# module.net
KiCad netlist of a schematic drawn in EAGLE
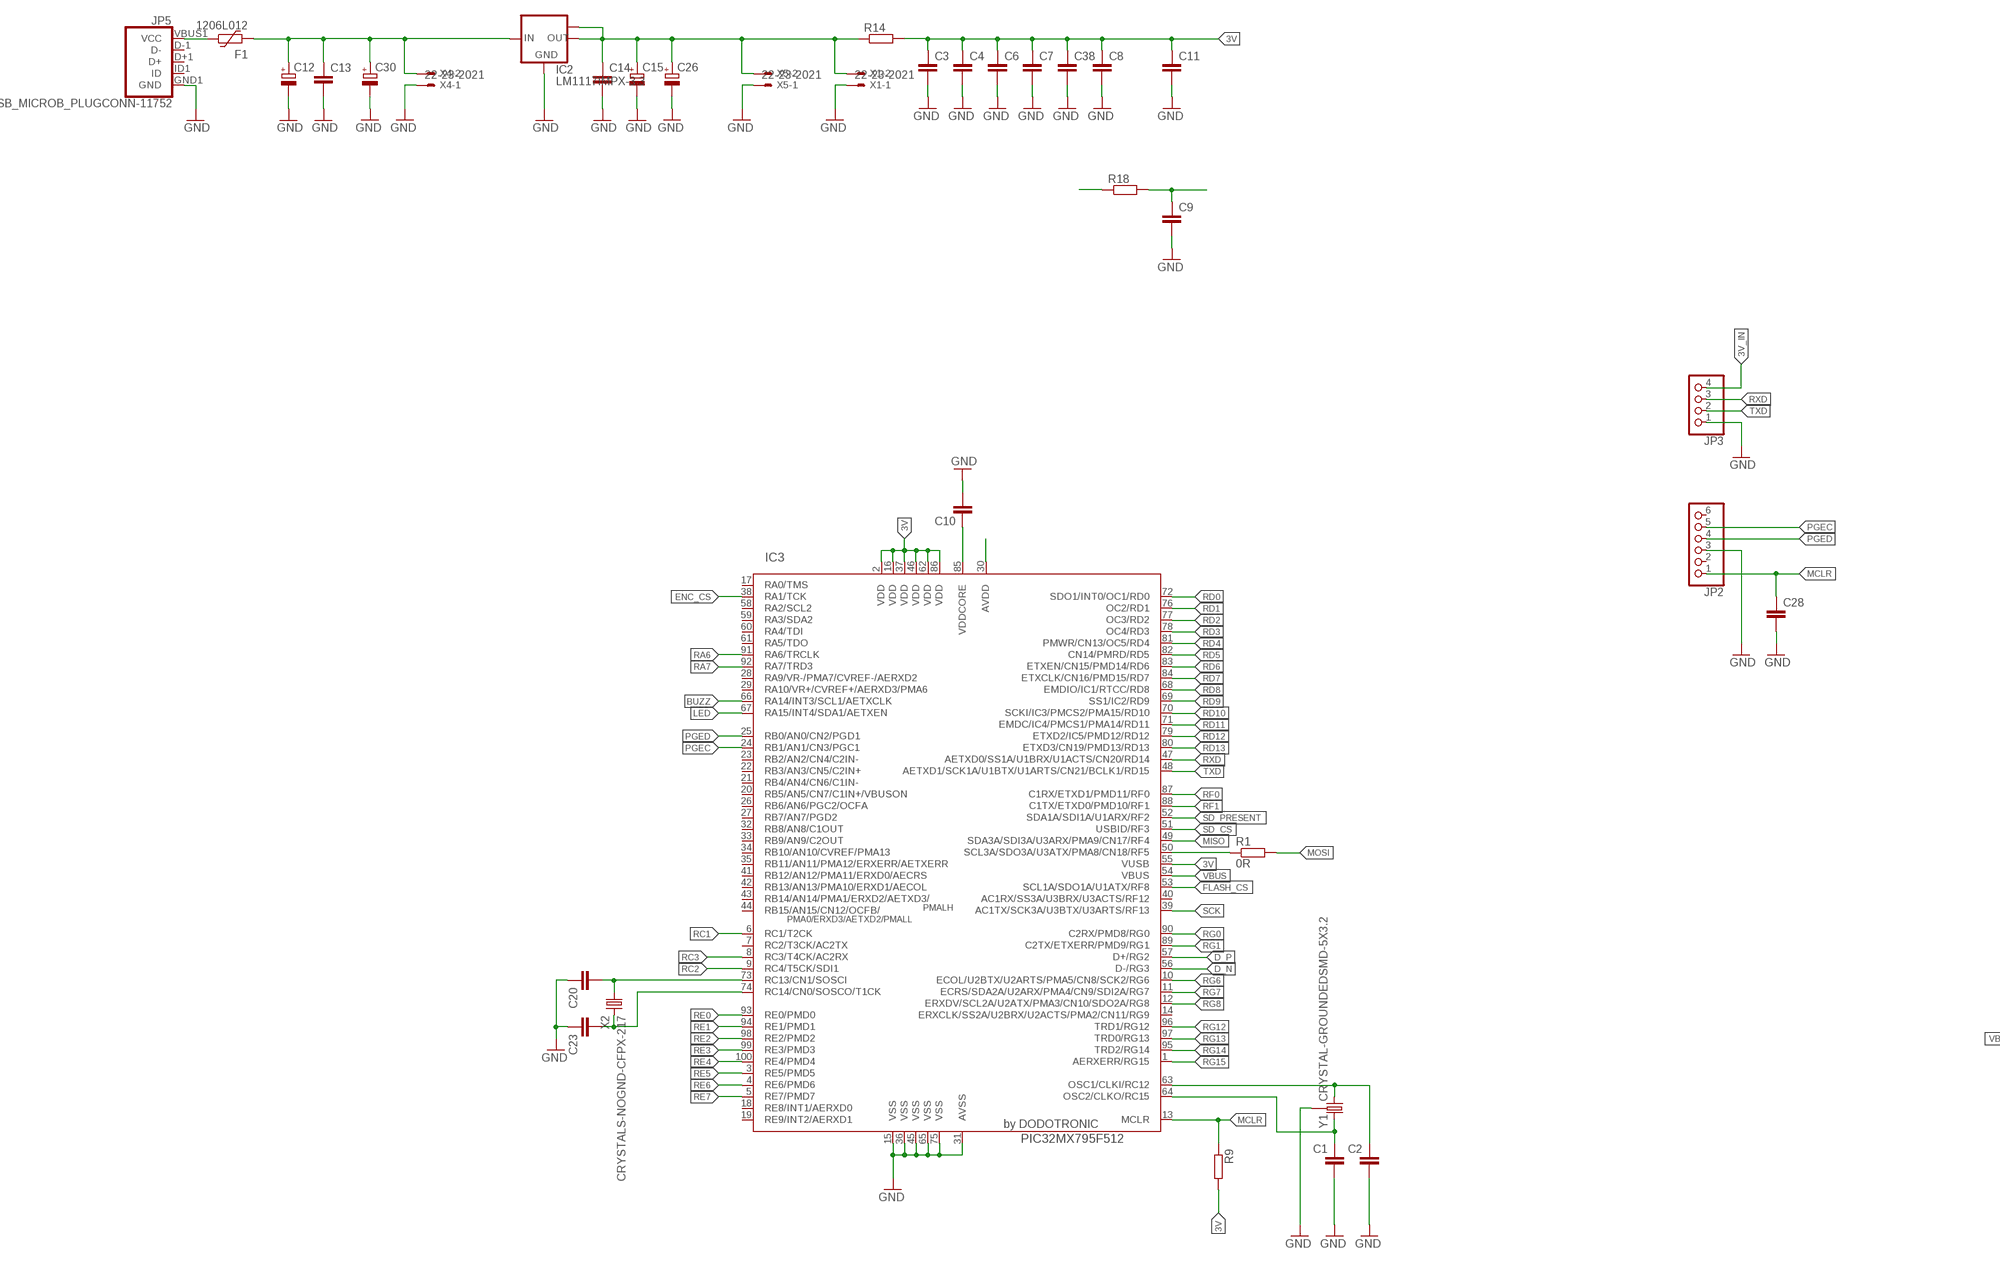
[diagram p0: schematic, sheet 1, part 1 of 3]
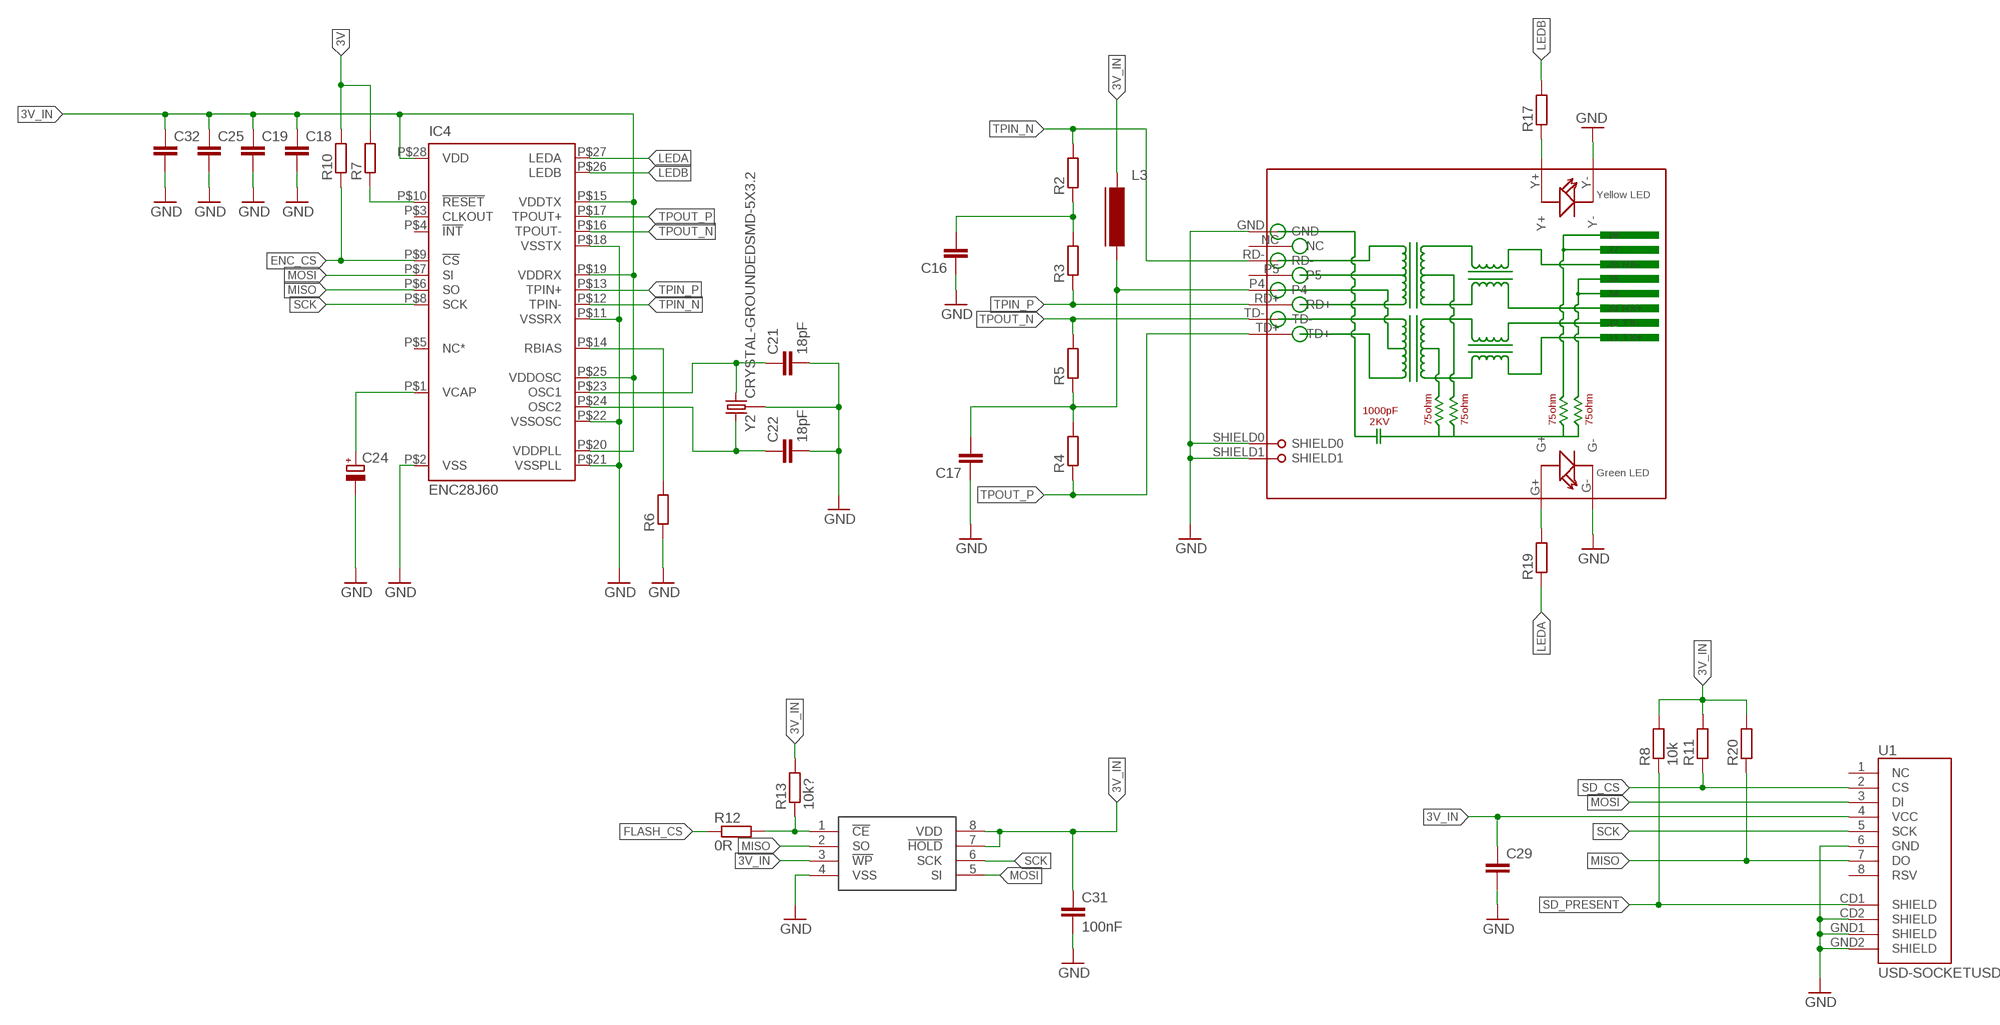
[diagram p1: schematic, sheet 1, part 2 of 3]
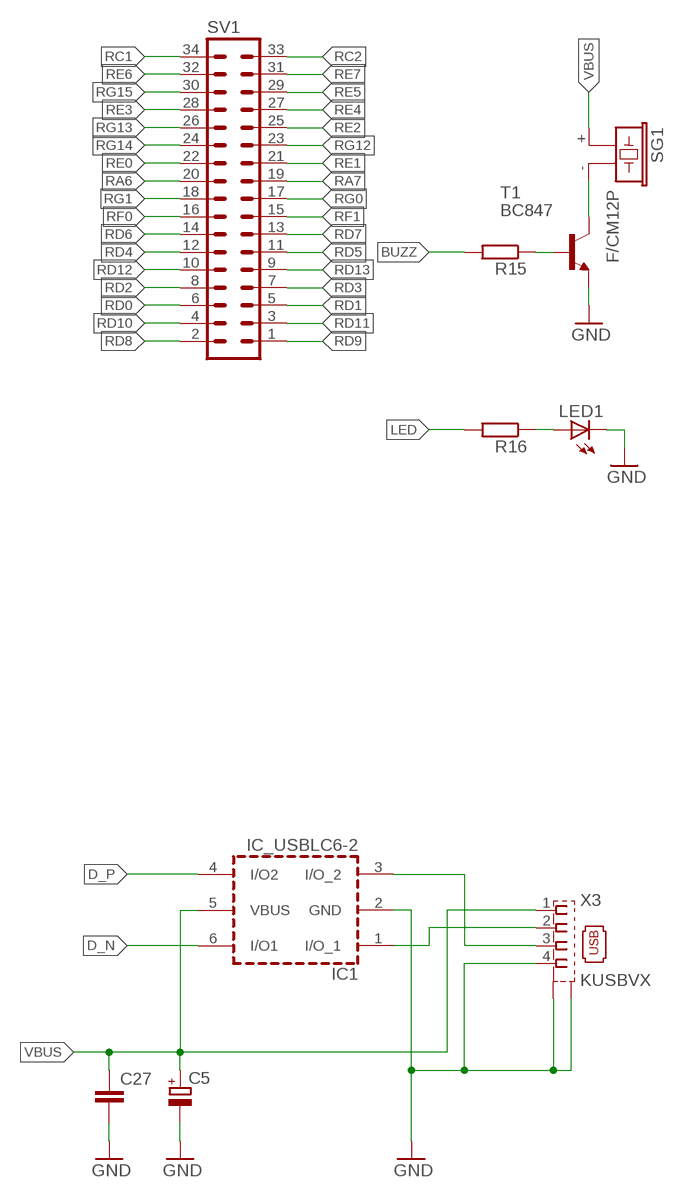
[diagram p2: schematic, sheet 1, part 3 of 3]

(export (version "E")
  (design (tool "Eeschema 10.0.6"))
  (components
    (comp (ref "C1")
      (value "C-EUC0603")
      (footprint "eagle-import:C0603")
      (libsource (lib "eagle-import") (part "C-EUC0603"))
    )
    (comp (ref "C2")
      (value "C-EUC0603")
      (footprint "eagle-import:C0603")
      (libsource (lib "eagle-import") (part "C-EUC0603"))
    )
    (comp (ref "C3")
      (value "C-EUC0402")
      (footprint "eagle-import:C0402")
      (libsource (lib "eagle-import") (part "C-EUC0402"))
    )
    (comp (ref "C4")
      (value "C-EUC0402")
      (footprint "eagle-import:C0402")
      (libsource (lib "eagle-import") (part "C-EUC0402"))
    )
    (comp (ref "C5")
      (value "CPOL-EUSMCA")
      (footprint "eagle-import:SMC_A")
      (libsource (lib "eagle-import") (part "CPOL-EUSMCA"))
    )
    (comp (ref "C6")
      (value "C-EUC0402")
      (footprint "eagle-import:C0402")
      (libsource (lib "eagle-import") (part "C-EUC0402"))
    )
    (comp (ref "C7")
      (value "C-EUC0402")
      (footprint "eagle-import:C0402")
      (libsource (lib "eagle-import") (part "C-EUC0402"))
    )
    (comp (ref "C8")
      (value "C-EUC0402")
      (footprint "eagle-import:C0402")
      (libsource (lib "eagle-import") (part "C-EUC0402"))
    )
    (comp (ref "C9")
      (value "C-EUC0402")
      (footprint "eagle-import:C0402")
      (libsource (lib "eagle-import") (part "C-EUC0402"))
    )
    (comp (ref "C10")
      (value "C-EUC0603")
      (footprint "eagle-import:C0603")
      (libsource (lib "eagle-import") (part "C-EUC0603"))
    )
    (comp (ref "C11")
      (value "C-EUC0402")
      (footprint "eagle-import:C0402")
      (libsource (lib "eagle-import") (part "C-EUC0402"))
    )
    (comp (ref "C12")
      (value "CPOL-EUSMCB")
      (footprint "eagle-import:SMC_B")
      (libsource (lib "eagle-import") (part "CPOL-EUSMCB"))
    )
    (comp (ref "C13")
      (value "C-EUC0603")
      (footprint "eagle-import:C0603")
      (libsource (lib "eagle-import") (part "C-EUC0603"))
    )
    (comp (ref "C14")
      (value "C-EUC0603")
      (footprint "eagle-import:C0603")
      (libsource (lib "eagle-import") (part "C-EUC0603"))
    )
    (comp (ref "C15")
      (value "CPOL-EUSMCB")
      (footprint "eagle-import:SMC_B")
      (libsource (lib "eagle-import") (part "CPOL-EUSMCB"))
    )
    (comp (ref "C16")
      (value "C-EUC0603")
      (footprint "eagle-import:C0603")
      (libsource (lib "eagle-import") (part "C-EUC0603"))
    )
    (comp (ref "C17")
      (value "C-EUC0603")
      (footprint "eagle-import:C0603")
      (libsource (lib "eagle-import") (part "C-EUC0603"))
    )
    (comp (ref "C18")
      (value "C-EUC0402")
      (footprint "eagle-import:C0402")
      (libsource (lib "eagle-import") (part "C-EUC0402"))
    )
    (comp (ref "C19")
      (value "C-EUC0603")
      (footprint "eagle-import:C0603")
      (libsource (lib "eagle-import") (part "C-EUC0603"))
    )
    (comp (ref "C20")
      (value "C-EUC0603")
      (footprint "eagle-import:C0603")
      (libsource (lib "eagle-import") (part "C-EUC0603"))
    )
    (comp (ref "C21")
      (value "18pF")
      (footprint "eagle-import:C0603")
      (libsource (lib "eagle-import") (part "C-EUC0603"))
    )
    (comp (ref "C22")
      (value "18pF")
      (footprint "eagle-import:C0603")
      (libsource (lib "eagle-import") (part "C-EUC0603"))
    )
    (comp (ref "C23")
      (value "C-EUC0603")
      (footprint "eagle-import:C0603")
      (libsource (lib "eagle-import") (part "C-EUC0603"))
    )
    (comp (ref "C24")
      (value "CPOL-EUSMCA")
      (footprint "eagle-import:SMC_A")
      (libsource (lib "eagle-import") (part "CPOL-EUSMCA"))
    )
    (comp (ref "C25")
      (value "C-EUC0603")
      (footprint "eagle-import:C0603")
      (libsource (lib "eagle-import") (part "C-EUC0603"))
    )
    (comp (ref "C26")
      (value "CPOL-EUSMCA")
      (footprint "eagle-import:SMC_A")
      (libsource (lib "eagle-import") (part "CPOL-EUSMCA"))
    )
    (comp (ref "C27")
      (value "C-EUC0603")
      (footprint "eagle-import:C0603")
      (libsource (lib "eagle-import") (part "C-EUC0603"))
    )
    (comp (ref "C28")
      (value "C-EUC0603")
      (footprint "eagle-import:C0603")
      (libsource (lib "eagle-import") (part "C-EUC0603"))
    )
    (comp (ref "C29")
      (value "C-EUC0603")
      (footprint "eagle-import:C0603")
      (libsource (lib "eagle-import") (part "C-EUC0603"))
    )
    (comp (ref "C30")
      (value "CPOL-EUSMCA")
      (footprint "eagle-import:SMC_A")
      (libsource (lib "eagle-import") (part "CPOL-EUSMCA"))
    )
    (comp (ref "C31")
      (value "100nF")
      (footprint "eagle-import:C0603")
      (libsource (lib "eagle-import") (part "C-EUC0603"))
    )
    (comp (ref "C32")
      (value "C-EUC0402")
      (footprint "eagle-import:C0402")
      (libsource (lib "eagle-import") (part "C-EUC0402"))
    )
    (comp (ref "C38")
      (value "C-EUC0603")
      (footprint "eagle-import:C0603")
      (libsource (lib "eagle-import") (part "C-EUC0603"))
    )
    (comp (ref "F1")
      (value "1206L012")
      (footprint "eagle-import:1206L")
      (fields (field (name "MF") "Littelfuse"))
      (libsource (lib "eagle-import") (part "?1206L012"))
    )
    (comp (ref "IC1")
      (value "IC_USBLC6-2")
      (footprint "eagle-import:SOT-23-6L")
      (libsource (lib "eagle-import") (part "IC_USBLC6-2"))
    )
    (comp (ref "IC2")
      (value "LM1117IMPX-3.3")
      (footprint "eagle-import:SOT223")
      (libsource (lib "eagle-import") (part "LM1117IMPX-3.3"))
    )
    (comp (ref "IC3")
      (value "PIC32MX795F512")
      (footprint "eagle-import:TQFP100_12X12")
      (libsource (lib "eagle-import") (part "PIC32MX795F512"))
    )
    (comp (ref "IC4")
      (value "ENC28J60")
      (footprint "eagle-import:TSSOP28W")
      (libsource (lib "eagle-import") (part "ENC28J60"))
    )
    (comp (ref "JP2")
      (value "PINHD-1X6")
      (footprint "eagle-import:1X06")
      (libsource (lib "eagle-import") (part "PINHD-1X6"))
    )
    (comp (ref "JP3")
      (value "PINHD-1X4")
      (footprint "eagle-import:1X04")
      (libsource (lib "eagle-import") (part "PINHD-1X4"))
    )
    (comp (ref "JP5")
      (value "USB_MICROB_PLUGCONN-11752")
      (footprint "eagle-import:USB-B-MICRO-SMD_V03")
      (libsource (lib "eagle-import") (part "USB_MICROB_PLUGCONN-11752"))
    )
    (comp (ref "L3")
      (value "FERRITE-0805")
      (footprint "eagle-import:FB805")
      (libsource (lib "eagle-import") (part "FERRITE-0805"))
    )
    (comp (ref "LED1")
      (value "LED3MM")
      (footprint "eagle-import:LED3MM")
      (libsource (lib "eagle-import") (part "LED3MM"))
    )
    (comp (ref "R1")
      (value "0R")
      (footprint "eagle-import:R0603")
      (libsource (lib "eagle-import") (part "R-EU_R0603"))
    )
    (comp (ref "R2")
      (value "R-EU_R0603")
      (footprint "eagle-import:R0603")
      (libsource (lib "eagle-import") (part "R-EU_R0603"))
    )
    (comp (ref "R3")
      (value "R-EU_R0603")
      (footprint "eagle-import:R0603")
      (libsource (lib "eagle-import") (part "R-EU_R0603"))
    )
    (comp (ref "R4")
      (value "R-EU_R0603")
      (footprint "eagle-import:R0603")
      (libsource (lib "eagle-import") (part "R-EU_R0603"))
    )
    (comp (ref "R5")
      (value "R-EU_R0603")
      (footprint "eagle-import:R0603")
      (libsource (lib "eagle-import") (part "R-EU_R0603"))
    )
    (comp (ref "R6")
      (value "R-EU_R0805")
      (footprint "eagle-import:R0805")
      (libsource (lib "eagle-import") (part "R-EU_R0805"))
    )
    (comp (ref "R7")
      (value "R-EU_R0402")
      (footprint "eagle-import:R0402")
      (libsource (lib "eagle-import") (part "R-EU_R0402"))
    )
    (comp (ref "R8")
      (value "10k")
      (footprint "eagle-import:R0603")
      (libsource (lib "eagle-import") (part "R-EU_R0603"))
    )
    (comp (ref "R9")
      (value "R-EU_R0603")
      (footprint "eagle-import:R0603")
      (libsource (lib "eagle-import") (part "R-EU_R0603"))
    )
    (comp (ref "R10")
      (value "R-EU_R0603")
      (footprint "eagle-import:R0603")
      (libsource (lib "eagle-import") (part "R-EU_R0603"))
    )
    (comp (ref "R11")
      (value "R-EU_R0603")
      (footprint "eagle-import:R0603")
      (libsource (lib "eagle-import") (part "R-EU_R0603"))
    )
    (comp (ref "R12")
      (value "0R")
      (footprint "eagle-import:R0603")
      (libsource (lib "eagle-import") (part "R-EU_R0603"))
    )
    (comp (ref "R13")
      (value "10k?")
      (footprint "eagle-import:R0603")
      (libsource (lib "eagle-import") (part "R-EU_R0603"))
    )
    (comp (ref "R14")
      (value "R-EU_R1206")
      (footprint "eagle-import:R1206")
      (libsource (lib "eagle-import") (part "R-EU_R1206"))
    )
    (comp (ref "R15")
      (value "R-EU_R0603")
      (footprint "eagle-import:R0603")
      (libsource (lib "eagle-import") (part "R-EU_R0603"))
    )
    (comp (ref "R16")
      (value "R-EU_R0603")
      (footprint "eagle-import:R0603")
      (libsource (lib "eagle-import") (part "R-EU_R0603"))
    )
    (comp (ref "R17")
      (value "R-EU_R1206")
      (footprint "eagle-import:R1206")
      (libsource (lib "eagle-import") (part "R-EU_R1206"))
    )
    (comp (ref "R18")
      (value "R-EU_R0805")
      (footprint "eagle-import:R0805")
      (libsource (lib "eagle-import") (part "R-EU_R0805"))
    )
    (comp (ref "R19")
      (value "R-EU_R1206")
      (footprint "eagle-import:R1206")
      (libsource (lib "eagle-import") (part "R-EU_R1206"))
    )
    (comp (ref "R20")
      (value "R-EU_R0603")
      (footprint "eagle-import:R0603")
      (libsource (lib "eagle-import") (part "R-EU_R0603"))
    )
    (comp (ref "RJ1")
      (value "HR911105A")
      (footprint "eagle-import:HR911105A")
      (libsource (lib "eagle-import") (part "HR911105A"))
    )
    (comp (ref "SG1")
      (value "F/CM12P")
      (footprint "eagle-import:F_CM12P")
      (libsource (lib "eagle-import") (part "F/CM12P"))
    )
    (comp (ref "SV1")
      (value "ML34L")
      (footprint "eagle-import:ML34L")
      (libsource (lib "eagle-import") (part "ML34L"))
    )
    (comp (ref "T1")
      (value "BC847")
      (footprint "eagle-import:SOT23")
      (libsource (lib "eagle-import") (part "BC847"))
    )
    (comp (ref "U$2")
      (value "SST25VF016BSO8M")
      (footprint "eagle-import:SO-08M")
      (libsource (lib "eagle-import") (part "SST25VF016BSO8M"))
    )
    (comp (ref "U1")
      (value "USD-SOCKETUSD")
      (footprint "eagle-import:USD-SOCKET-PP")
      (libsource (lib "eagle-import") (part "USD-SOCKETUSD"))
    )
    (comp (ref "X1")
      (value "22-23-2021")
      (footprint "eagle-import:22-23-2021")
      (fields (field (name "MF") "MOLEX"))
      (libsource (lib "eagle-import") (part "22-23-2021"))
    )
    (comp (ref "X2")
      (value "CRYSTALS-NOGND-CFPX-217")
      (footprint "eagle-import:3.2X1.5-2-PAD")
      (libsource (lib "eagle-import") (part "CRYSTALS-NOGND-CFPX-217"))
    )
    (comp (ref "X3")
      (value "KUSBVX")
      (footprint "eagle-import:KUSBVX")
      (libsource (lib "eagle-import") (part "KUSBVX"))
    )
    (comp (ref "X4")
      (value "22-23-2021")
      (footprint "eagle-import:22-23-2021")
      (fields (field (name "MF") "MOLEX"))
      (libsource (lib "eagle-import") (part "22-23-2021"))
    )
    (comp (ref "X5")
      (value "22-23-2021")
      (footprint "eagle-import:22-23-2021")
      (fields (field (name "MF") "MOLEX"))
      (libsource (lib "eagle-import") (part "22-23-2021"))
    )
    (comp (ref "Y1")
      (value "CRYSTAL-GROUNDEDSMD-5X3.2")
      (footprint "eagle-import:CRYSTAL-SMD-5X3.2-4PAD")
      (libsource (lib "eagle-import") (part "CRYSTAL-GROUNDEDSMD-5X3.2"))
    )
    (comp (ref "Y2")
      (value "CRYSTAL-GROUNDEDSMD-5X3.2")
      (footprint "eagle-import:CRYSTAL-SMD-5X3.2-4PAD")
      (libsource (lib "eagle-import") (part "CRYSTAL-GROUNDEDSMD-5X3.2"))
    )
  )
  (nets
    (net (code "1") (name "/AN_3V") (class "Default")
      (node (ref "C9") (pin "1") (pinfunction "1_1") (pintype "passive"))
      (node (ref "IC3") (pin "30") (pinfunction "AVDD_30") (pintype "bidirectional"))
      (node (ref "R18") (pin "2") (pinfunction "2_2") (pintype "passive"))
    )
    (net (code "2") (name "3V") (class "Default")
      (node (ref "C11") (pin "1") (pinfunction "1_1") (pintype "passive"))
      (node (ref "C3") (pin "1") (pinfunction "1_1") (pintype "passive"))
      (node (ref "C38") (pin "1") (pinfunction "1_1") (pintype "passive"))
      (node (ref "C4") (pin "1") (pinfunction "1_1") (pintype "passive"))
      (node (ref "C6") (pin "1") (pinfunction "1_1") (pintype "passive"))
      (node (ref "C7") (pin "1") (pinfunction "1_1") (pintype "passive"))
      (node (ref "C8") (pin "1") (pinfunction "1_1") (pintype "passive"))
      (node (ref "IC3") (pin "16") (pinfunction "VDD_16") (pintype "power_in"))
      (node (ref "IC3") (pin "2") (pinfunction "VDD_2") (pintype "power_in"))
      (node (ref "IC3") (pin "37") (pinfunction "VDD_37") (pintype "power_in"))
      (node (ref "IC3") (pin "46") (pinfunction "VDD_46") (pintype "power_in"))
      (node (ref "IC3") (pin "55") (pinfunction "VUSB_55") (pintype "bidirectional"))
      (node (ref "IC3") (pin "62") (pinfunction "VDD_62") (pintype "power_in"))
      (node (ref "IC3") (pin "86") (pinfunction "VDD_86") (pintype "power_in"))
      (node (ref "R10") (pin "2") (pinfunction "2_2") (pintype "passive"))
      (node (ref "R14") (pin "2") (pinfunction "2_2") (pintype "passive"))
      (node (ref "R18") (pin "1") (pinfunction "1_1") (pintype "passive"))
      (node (ref "R7") (pin "2") (pinfunction "2_2") (pintype "passive"))
      (node (ref "R9") (pin "2") (pinfunction "2_2") (pintype "passive"))
    )
    (net (code "3") (name "3V_IN") (class "Default")
      (node (ref "C14") (pin "1") (pinfunction "1_1") (pintype "passive"))
      (node (ref "C15") (pin "+") (pinfunction "+_+") (pintype "passive"))
      (node (ref "C18") (pin "1") (pinfunction "1_1") (pintype "passive"))
      (node (ref "C19") (pin "1") (pinfunction "1_1") (pintype "passive"))
      (node (ref "C25") (pin "1") (pinfunction "1_1") (pintype "passive"))
      (node (ref "C26") (pin "+") (pinfunction "+_+") (pintype "passive"))
      (node (ref "C29") (pin "1") (pinfunction "1_1") (pintype "passive"))
      (node (ref "C31") (pin "1") (pinfunction "1_1") (pintype "passive"))
      (node (ref "C32") (pin "1") (pinfunction "1_1") (pintype "passive"))
      (node (ref "IC2") (pin "2") (pinfunction "OUT_2") (pintype "passive"))
      (node (ref "IC2") (pin "TAB") (pinfunction "OUT1_TAB") (pintype "passive"))
      (node (ref "IC4") (pin "P$15") (pinfunction "VDDTX_P$15") (pintype "input"))
      (node (ref "IC4") (pin "P$19") (pinfunction "VDDRX_P$19") (pintype "input"))
      (node (ref "IC4") (pin "P$20") (pinfunction "VDDPLL_P$20") (pintype "input"))
      (node (ref "IC4") (pin "P$25") (pinfunction "VDDOSC_P$25") (pintype "input"))
      (node (ref "IC4") (pin "P$28") (pinfunction "VDD_P$28") (pintype "input"))
      (node (ref "JP3") (pin "4") (pinfunction "4_4") (pintype "passive"))
      (node (ref "L3") (pin "1") (pinfunction "1_1") (pintype "passive"))
      (node (ref "R11") (pin "2") (pinfunction "2_2") (pintype "passive"))
      (node (ref "R13") (pin "2") (pinfunction "2_2") (pintype "passive"))
      (node (ref "R14") (pin "1") (pinfunction "1_1") (pintype "passive"))
      (node (ref "R20") (pin "2") (pinfunction "2_2") (pintype "passive"))
      (node (ref "R8") (pin "2") (pinfunction "2_2") (pintype "passive"))
      (node (ref "U$2") (pin "3") (pinfunction "~{WP}_3") (pintype "bidirectional"))
      (node (ref "U$2") (pin "7") (pinfunction "~{HOLD}_7") (pintype "bidirectional"))
      (node (ref "U$2") (pin "8") (pinfunction "VDD_8") (pintype "bidirectional"))
      (node (ref "U1") (pin "4") (pinfunction "VCC_4") (pintype "bidirectional"))
      (node (ref "X1") (pin "2") (pinfunction "S_2") (pintype "passive"))
      (node (ref "X5") (pin "2") (pinfunction "S_2") (pintype "passive"))
    )
    (net (code "4") (name "BUZZ") (class "Default")
      (node (ref "IC3") (pin "66") (pinfunction "RA14/INT3/SCL1/AETXCLK_66") (pintype "bidirectional"))
      (node (ref "R15") (pin "2") (pinfunction "2_2") (pintype "passive"))
    )
    (net (code "5") (name "D_N") (class "Default")
      (node (ref "IC1") (pin "6") (pinfunction "I/O1_6") (pintype "bidirectional"))
      (node (ref "IC3") (pin "56") (pinfunction "D-/RG3_56") (pintype "bidirectional"))
    )
    (net (code "6") (name "D_P") (class "Default")
      (node (ref "IC1") (pin "4") (pinfunction "I/O2_4") (pintype "bidirectional"))
      (node (ref "IC3") (pin "57") (pinfunction "D+/RG2_57") (pintype "bidirectional"))
    )
    (net (code "7") (name "ENC_CS") (class "Default")
      (node (ref "IC3") (pin "38") (pinfunction "RA1/TCK_38") (pintype "bidirectional"))
      (node (ref "IC4") (pin "P$9") (pinfunction "~{CS}_P$9") (pintype "input"))
      (node (ref "R10") (pin "1") (pinfunction "1_1") (pintype "passive"))
    )
    (net (code "8") (name "FLASH_CS") (class "Default")
      (node (ref "IC3") (pin "53") (pinfunction "SCL1A/SDO1A/U1ATX/RF8_53") (pintype "bidirectional"))
      (node (ref "R12") (pin "1") (pinfunction "1_1") (pintype "passive"))
    )
    (net (code "9") (name "GND") (class "Default")
      (node (ref "C1") (pin "2") (pinfunction "2_2") (pintype "passive"))
      (node (ref "C10") (pin "2") (pinfunction "2_2") (pintype "passive"))
      (node (ref "C11") (pin "2") (pinfunction "2_2") (pintype "passive"))
      (node (ref "C12") (pin "-") (pinfunction "-_-") (pintype "passive"))
      (node (ref "C13") (pin "2") (pinfunction "2_2") (pintype "passive"))
      (node (ref "C14") (pin "2") (pinfunction "2_2") (pintype "passive"))
      (node (ref "C15") (pin "-") (pinfunction "-_-") (pintype "passive"))
      (node (ref "C16") (pin "1") (pinfunction "1_1") (pintype "passive"))
      (node (ref "C17") (pin "1") (pinfunction "1_1") (pintype "passive"))
      (node (ref "C18") (pin "2") (pinfunction "2_2") (pintype "passive"))
      (node (ref "C19") (pin "2") (pinfunction "2_2") (pintype "passive"))
      (node (ref "C2") (pin "2") (pinfunction "2_2") (pintype "passive"))
      (node (ref "C20") (pin "1") (pinfunction "1_1") (pintype "passive"))
      (node (ref "C21") (pin "2") (pinfunction "2_2") (pintype "passive"))
      (node (ref "C22") (pin "2") (pinfunction "2_2") (pintype "passive"))
      (node (ref "C23") (pin "1") (pinfunction "1_1") (pintype "passive"))
      (node (ref "C24") (pin "-") (pinfunction "-_-") (pintype "passive"))
      (node (ref "C25") (pin "2") (pinfunction "2_2") (pintype "passive"))
      (node (ref "C26") (pin "-") (pinfunction "-_-") (pintype "passive"))
      (node (ref "C27") (pin "2") (pinfunction "2_2") (pintype "passive"))
      (node (ref "C28") (pin "2") (pinfunction "2_2") (pintype "passive"))
      (node (ref "C29") (pin "2") (pinfunction "2_2") (pintype "passive"))
      (node (ref "C3") (pin "2") (pinfunction "2_2") (pintype "passive"))
      (node (ref "C30") (pin "-") (pinfunction "-_-") (pintype "passive"))
      (node (ref "C31") (pin "2") (pinfunction "2_2") (pintype "passive"))
      (node (ref "C32") (pin "2") (pinfunction "2_2") (pintype "passive"))
      (node (ref "C38") (pin "2") (pinfunction "2_2") (pintype "passive"))
      (node (ref "C4") (pin "2") (pinfunction "2_2") (pintype "passive"))
      (node (ref "C5") (pin "-") (pinfunction "-_-") (pintype "passive"))
      (node (ref "C6") (pin "2") (pinfunction "2_2") (pintype "passive"))
      (node (ref "C7") (pin "2") (pinfunction "2_2") (pintype "passive"))
      (node (ref "C8") (pin "2") (pinfunction "2_2") (pintype "passive"))
      (node (ref "C9") (pin "2") (pinfunction "2_2") (pintype "passive"))
      (node (ref "IC1") (pin "2") (pinfunction "GND_2") (pintype "bidirectional"))
      (node (ref "IC2") (pin "1") (pinfunction "GND_1") (pintype "input"))
      (node (ref "IC3") (pin "15") (pinfunction "VSS_15") (pintype "power_in"))
      (node (ref "IC3") (pin "31") (pinfunction "AVSS_31") (pintype "bidirectional"))
      (node (ref "IC3") (pin "36") (pinfunction "VSS_36") (pintype "power_in"))
      (node (ref "IC3") (pin "45") (pinfunction "VSS_45") (pintype "power_in"))
      (node (ref "IC3") (pin "65") (pinfunction "VSS_65") (pintype "power_in"))
      (node (ref "IC3") (pin "75") (pinfunction "VSS_75") (pintype "power_in"))
      (node (ref "IC4") (pin "P$11") (pinfunction "VSSRX_P$11") (pintype "input"))
      (node (ref "IC4") (pin "P$18") (pinfunction "VSSTX_P$18") (pintype "input"))
      (node (ref "IC4") (pin "P$2") (pinfunction "VSS_P$2") (pintype "input"))
      (node (ref "IC4") (pin "P$21") (pinfunction "VSSPLL_P$21") (pintype "input"))
      (node (ref "IC4") (pin "P$22") (pinfunction "VSSOSC_P$22") (pintype "input"))
      (node (ref "JP2") (pin "3") (pinfunction "3_3") (pintype "passive"))
      (node (ref "JP3") (pin "1") (pinfunction "1_1") (pintype "passive"))
      (node (ref "JP5") (pin "GND1") (pinfunction "GND_GND1") (pintype "bidirectional"))
      (node (ref "LED1") (pin "K") (pinfunction "C_K") (pintype "passive"))
      (node (ref "R6") (pin "1") (pinfunction "1_1") (pintype "passive"))
      (node (ref "RJ1") (pin "G-") (pinfunction "G-_G-") (pintype "bidirectional"))
      (node (ref "RJ1") (pin "GND") (pinfunction "GND_GND") (pintype "bidirectional"))
      (node (ref "RJ1") (pin "SHIELD0") (pinfunction "SHIELD0_SHIELD0") (pintype "bidirectional"))
      (node (ref "RJ1") (pin "SHIELD1") (pinfunction "SHIELD1_SHIELD1") (pintype "bidirectional"))
      (node (ref "RJ1") (pin "Y-") (pinfunction "Y-_Y-") (pintype "bidirectional"))
      (node (ref "T1") (pin "2") (pinfunction "E_2") (pintype "passive"))
      (node (ref "U$2") (pin "4") (pinfunction "VSS_4") (pintype "bidirectional"))
      (node (ref "U1") (pin "6") (pinfunction "GND_6") (pintype "bidirectional"))
      (node (ref "U1") (pin "CD2") (pinfunction "SHIELD_CD2") (pintype "bidirectional"))
      (node (ref "U1") (pin "GND1") (pinfunction "SHIELD_GND1") (pintype "bidirectional"))
      (node (ref "U1") (pin "GND2") (pinfunction "SHIELD_GND2") (pintype "bidirectional"))
      (node (ref "X1") (pin "1") (pinfunction "S_1") (pintype "passive"))
      (node (ref "X3") (pin "4") (pinfunction "4_4") (pintype "passive"))
      (node (ref "X3") (pin "M1") (pinfunction "S1_M1") (pintype "passive"))
      (node (ref "X3") (pin "M2") (pinfunction "S2_M2") (pintype "passive"))
      (node (ref "X4") (pin "1") (pinfunction "S_1") (pintype "passive"))
      (node (ref "X5") (pin "1") (pinfunction "S_1") (pintype "passive"))
      (node (ref "Y1") (pin "2") (pinfunction "3_2") (pintype "passive"))
      (node (ref "Y1") (pin "4") (pinfunction "3_4") (pintype "passive"))
      (node (ref "Y2") (pin "2") (pinfunction "3_2") (pintype "passive"))
      (node (ref "Y2") (pin "4") (pinfunction "3_4") (pintype "passive"))
    )
    (net (code "10") (name "LED") (class "Default")
      (node (ref "IC3") (pin "67") (pinfunction "RA15/INT4/SDA1/AETXEN_67") (pintype "bidirectional"))
      (node (ref "R16") (pin "2") (pinfunction "2_2") (pintype "passive"))
    )
    (net (code "11") (name "LEDA") (class "Default")
      (node (ref "IC4") (pin "P$27") (pinfunction "LEDA_P$27") (pintype "output"))
      (node (ref "R19") (pin "1") (pinfunction "1_1") (pintype "passive"))
    )
    (net (code "12") (name "LEDB") (class "Default")
      (node (ref "IC4") (pin "P$26") (pinfunction "LEDB_P$26") (pintype "output"))
      (node (ref "R17") (pin "2") (pinfunction "2_2") (pintype "passive"))
    )
    (net (code "13") (name "MCLR") (class "Default")
      (node (ref "C28") (pin "1") (pinfunction "1_1") (pintype "passive"))
      (node (ref "IC3") (pin "13") (pinfunction "MCLR_13") (pintype "bidirectional"))
      (node (ref "JP2") (pin "1") (pinfunction "1_1") (pintype "passive"))
      (node (ref "R9") (pin "1") (pinfunction "1_1") (pintype "passive"))
    )
    (net (code "14") (name "MISO") (class "Default")
      (node (ref "IC3") (pin "49") (pinfunction "SDA3A/SDI3A/U3ARX/PMA9/CN17/RF4_49") (pintype "bidirectional"))
      (node (ref "IC4") (pin "P$6") (pinfunction "SO_P$6") (pintype "output"))
      (node (ref "R20") (pin "1") (pinfunction "1_1") (pintype "passive"))
      (node (ref "U$2") (pin "2") (pinfunction "SO_2") (pintype "bidirectional"))
      (node (ref "U1") (pin "7") (pinfunction "DO_7") (pintype "bidirectional"))
    )
    (net (code "15") (name "MOSI") (class "Default")
      (node (ref "IC4") (pin "P$7") (pinfunction "SI_P$7") (pintype "input"))
      (node (ref "R1") (pin "2") (pinfunction "2_2") (pintype "passive"))
      (node (ref "U$2") (pin "5") (pinfunction "SI_5") (pintype "bidirectional"))
      (node (ref "U1") (pin "3") (pinfunction "DI_3") (pintype "bidirectional"))
    )
    (net (code "16") (name "Net-(C16-Pad2)") (class "Default")
      (node (ref "C16") (pin "2") (pinfunction "2_2") (pintype "passive"))
      (node (ref "R2") (pin "1") (pinfunction "1_1") (pintype "passive"))
      (node (ref "R3") (pin "2") (pinfunction "2_2") (pintype "passive"))
    )
    (net (code "17") (name "Net-(C17-Pad2)") (class "Default")
      (node (ref "C17") (pin "2") (pinfunction "2_2") (pintype "passive"))
      (node (ref "L3") (pin "2") (pinfunction "2_2") (pintype "passive"))
      (node (ref "R4") (pin "2") (pinfunction "2_2") (pintype "passive"))
      (node (ref "R5") (pin "1") (pinfunction "1_1") (pintype "passive"))
      (node (ref "RJ1") (pin "P4") (pinfunction "P4_P4") (pintype "bidirectional"))
    )
    (net (code "18") (name "Net-(IC1-I{slash}O_1)") (class "Default")
      (node (ref "IC1") (pin "1") (pinfunction "I/O_1_1") (pintype "bidirectional"))
      (node (ref "X3") (pin "2") (pinfunction "2_2") (pintype "passive"))
    )
    (net (code "19") (name "Net-(IC1-I{slash}O_2)") (class "Default")
      (node (ref "IC1") (pin "3") (pinfunction "I/O_2_3") (pintype "bidirectional"))
      (node (ref "X3") (pin "3") (pinfunction "3_3") (pintype "passive"))
    )
    (net (code "20") (name "Net-(IC3-OSC1{slash}CLKI{slash}RC12)") (class "Default")
      (node (ref "C2") (pin "1") (pinfunction "1_1") (pintype "passive"))
      (node (ref "IC3") (pin "63") (pinfunction "OSC1/CLKI/RC12_63") (pintype "bidirectional"))
      (node (ref "Y1") (pin "1") (pinfunction "2_1") (pintype "passive"))
    )
    (net (code "21") (name "Net-(IC3-OSC2{slash}CLKO{slash}RC15)") (class "Default")
      (node (ref "C1") (pin "1") (pinfunction "1_1") (pintype "passive"))
      (node (ref "IC3") (pin "64") (pinfunction "OSC2/CLKO/RC15_64") (pintype "bidirectional"))
      (node (ref "Y1") (pin "3") (pinfunction "1_3") (pintype "passive"))
    )
    (net (code "22") (name "Net-(IC3-RC13{slash}CN1{slash}SOSCI)") (class "Default")
      (node (ref "C20") (pin "2") (pinfunction "2_2") (pintype "passive"))
      (node (ref "IC3") (pin "73") (pinfunction "RC13/CN1/SOSCI_73") (pintype "bidirectional"))
      (node (ref "X2") (pin "1") (pinfunction "1_1") (pintype "passive"))
    )
    (net (code "23") (name "Net-(IC3-RC14{slash}CN0{slash}SOSCO{slash}T1CK)") (class "Default")
      (node (ref "C23") (pin "2") (pinfunction "2_2") (pintype "passive"))
      (node (ref "IC3") (pin "74") (pinfunction "RC14/CN0/SOSCO/T1CK_74") (pintype "bidirectional"))
      (node (ref "X2") (pin "2") (pinfunction "2_2") (pintype "passive"))
    )
    (net (code "24") (name "Net-(IC3-SCL3A{slash}SDO3A{slash}U3ATX{slash}PMA8{slash}CN18{slash}RF5)") (class "Default")
      (node (ref "IC3") (pin "50") (pinfunction "SCL3A/SDO3A/U3ATX/PMA8/CN18/RF5_50") (pintype "bidirectional"))
      (node (ref "R1") (pin "1") (pinfunction "1_1") (pintype "passive"))
    )
    (net (code "25") (name "Net-(IC3-VDDCORE)") (class "Default")
      (node (ref "C10") (pin "1") (pinfunction "1_1") (pintype "passive"))
      (node (ref "IC3") (pin "85") (pinfunction "VDDCORE_85") (pintype "bidirectional"))
    )
    (net (code "26") (name "Net-(IC4-OSC1)") (class "Default")
      (node (ref "C21") (pin "1") (pinfunction "1_1") (pintype "passive"))
      (node (ref "IC4") (pin "P$23") (pinfunction "OSC1_P$23") (pintype "input"))
      (node (ref "Y2") (pin "1") (pinfunction "2_1") (pintype "passive"))
    )
    (net (code "27") (name "Net-(IC4-OSC2)") (class "Default")
      (node (ref "C22") (pin "1") (pinfunction "1_1") (pintype "passive"))
      (node (ref "IC4") (pin "P$24") (pinfunction "OSC2_P$24") (pintype "output"))
      (node (ref "Y2") (pin "3") (pinfunction "1_3") (pintype "passive"))
    )
    (net (code "28") (name "Net-(IC4-RBIAS)") (class "Default")
      (node (ref "IC4") (pin "P$14") (pinfunction "RBIAS_P$14") (pintype "input"))
      (node (ref "R6") (pin "2") (pinfunction "2_2") (pintype "passive"))
    )
    (net (code "29") (name "Net-(IC4-VCAP)") (class "Default")
      (node (ref "C24") (pin "+") (pinfunction "+_+") (pintype "passive"))
      (node (ref "IC4") (pin "P$1") (pinfunction "VCAP_P$1") (pintype "input"))
    )
    (net (code "30") (name "Net-(IC4-~{RESET})") (class "Default")
      (node (ref "IC4") (pin "P$10") (pinfunction "~{RESET}_P$10") (pintype "input"))
      (node (ref "R7") (pin "1") (pinfunction "1_1") (pintype "passive"))
    )
    (net (code "31") (name "Net-(JP5-VCC)") (class "Default")
      (node (ref "F1") (pin "1") (pinfunction "1_1") (pintype "passive"))
      (node (ref "JP5") (pin "VBUS1") (pinfunction "VCC_VBUS1") (pintype "bidirectional"))
    )
    (net (code "32") (name "Net-(LED1-PadA)") (class "Default")
      (node (ref "LED1") (pin "A") (pinfunction "A_A") (pintype "passive"))
      (node (ref "R16") (pin "1") (pinfunction "1_1") (pintype "passive"))
    )
    (net (code "33") (name "Net-(R17-Pad1)") (class "Default")
      (node (ref "R17") (pin "1") (pinfunction "1_1") (pintype "passive"))
      (node (ref "RJ1") (pin "Y+") (pinfunction "Y+_Y+") (pintype "bidirectional"))
    )
    (net (code "34") (name "Net-(R19-Pad2)") (class "Default")
      (node (ref "R19") (pin "2") (pinfunction "2_2") (pintype "passive"))
      (node (ref "RJ1") (pin "G+") (pinfunction "G+_G+") (pintype "bidirectional"))
    )
    (net (code "35") (name "Net-(SG1-2)") (class "Default")
      (node (ref "SG1") (pin "-") (pinfunction "2_-") (pintype "passive"))
      (node (ref "T1") (pin "3") (pinfunction "C_3") (pintype "passive"))
    )
    (net (code "36") (name "Net-(T1-B)") (class "Default")
      (node (ref "R15") (pin "1") (pinfunction "1_1") (pintype "passive"))
      (node (ref "T1") (pin "1") (pinfunction "B_1") (pintype "passive"))
    )
    (net (code "37") (name "Net-(U$2-~{CE})") (class "Default")
      (node (ref "R12") (pin "2") (pinfunction "2_2") (pintype "passive"))
      (node (ref "R13") (pin "1") (pinfunction "1_1") (pintype "passive"))
      (node (ref "U$2") (pin "1") (pinfunction "~{CE}_1") (pintype "bidirectional"))
    )
    (net (code "38") (name "PGEC") (class "Default")
      (node (ref "IC3") (pin "24") (pinfunction "RB1/AN1/CN3/PGC1_24") (pintype "bidirectional"))
      (node (ref "JP2") (pin "5") (pinfunction "5_5") (pintype "passive"))
    )
    (net (code "39") (name "PGED") (class "Default")
      (node (ref "IC3") (pin "25") (pinfunction "RB0/AN0/CN2/PGD1_25") (pintype "bidirectional"))
      (node (ref "JP2") (pin "4") (pinfunction "4_4") (pintype "passive"))
    )
    (net (code "40") (name "RA6") (class "Default")
      (node (ref "IC3") (pin "91") (pinfunction "RA6/TRCLK_91") (pintype "bidirectional"))
      (node (ref "SV1") (pin "20") (pinfunction "20_20") (pintype "passive"))
    )
    (net (code "41") (name "RA7") (class "Default")
      (node (ref "IC3") (pin "92") (pinfunction "RA7/TRD3_92") (pintype "bidirectional"))
      (node (ref "SV1") (pin "19") (pinfunction "19_19") (pintype "passive"))
    )
    (net (code "42") (name "RC1") (class "Default")
      (node (ref "IC3") (pin "6") (pinfunction "RC1/T2CK_6") (pintype "bidirectional"))
      (node (ref "SV1") (pin "34") (pinfunction "34_34") (pintype "passive"))
    )
    (net (code "43") (name "RC2") (class "Default")
      (node (ref "IC3") (pin "9") (pinfunction "RC4/T5CK/SDI1_9") (pintype "bidirectional"))
      (node (ref "SV1") (pin "33") (pinfunction "33_33") (pintype "passive"))
    )
    (net (code "44") (name "RC3") (class "Default")
      (node (ref "IC3") (pin "8") (pinfunction "RC3/T4CK/AC2RX_8") (pintype "bidirectional"))
    )
    (net (code "45") (name "RD0") (class "Default")
      (node (ref "IC3") (pin "72") (pinfunction "SDO1/INT0/OC1/RD0_72") (pintype "bidirectional"))
      (node (ref "SV1") (pin "6") (pinfunction "6_6") (pintype "passive"))
    )
    (net (code "46") (name "RD1") (class "Default")
      (node (ref "IC3") (pin "76") (pinfunction "OC2/RD1_76") (pintype "bidirectional"))
      (node (ref "SV1") (pin "5") (pinfunction "5_5") (pintype "passive"))
    )
    (net (code "47") (name "RD2") (class "Default")
      (node (ref "IC3") (pin "77") (pinfunction "OC3/RD2_77") (pintype "bidirectional"))
      (node (ref "SV1") (pin "8") (pinfunction "8_8") (pintype "passive"))
    )
    (net (code "48") (name "RD3") (class "Default")
      (node (ref "IC3") (pin "78") (pinfunction "OC4/RD3_78") (pintype "bidirectional"))
      (node (ref "SV1") (pin "7") (pinfunction "7_7") (pintype "passive"))
    )
    (net (code "49") (name "RD4") (class "Default")
      (node (ref "IC3") (pin "81") (pinfunction "PMWR/CN13/OC5/RD4_81") (pintype "bidirectional"))
      (node (ref "SV1") (pin "12") (pinfunction "12_12") (pintype "passive"))
    )
    (net (code "50") (name "RD5") (class "Default")
      (node (ref "IC3") (pin "82") (pinfunction "CN14/PMRD/RD5_82") (pintype "bidirectional"))
      (node (ref "SV1") (pin "11") (pinfunction "11_11") (pintype "passive"))
    )
    (net (code "51") (name "RD6") (class "Default")
      (node (ref "IC3") (pin "83") (pinfunction "ETXEN/CN15/PMD14/RD6_83") (pintype "bidirectional"))
      (node (ref "SV1") (pin "14") (pinfunction "14_14") (pintype "passive"))
    )
    (net (code "52") (name "RD7") (class "Default")
      (node (ref "IC3") (pin "84") (pinfunction "ETXCLK/CN16/PMD15/RD7_84") (pintype "bidirectional"))
      (node (ref "SV1") (pin "13") (pinfunction "13_13") (pintype "passive"))
    )
    (net (code "53") (name "RD8") (class "Default")
      (node (ref "IC3") (pin "68") (pinfunction "EMDIO/IC1/RTCC/RD8_68") (pintype "bidirectional"))
      (node (ref "SV1") (pin "2") (pinfunction "2_2") (pintype "passive"))
    )
    (net (code "54") (name "RD9") (class "Default")
      (node (ref "IC3") (pin "69") (pinfunction "SS1/IC2/RD9_69") (pintype "bidirectional"))
      (node (ref "SV1") (pin "1") (pinfunction "1_1") (pintype "passive"))
    )
    (net (code "55") (name "RD10") (class "Default")
      (node (ref "IC3") (pin "70") (pinfunction "SCKI/IC3/PMCS2/PMA15/RD10_70") (pintype "bidirectional"))
      (node (ref "SV1") (pin "4") (pinfunction "4_4") (pintype "passive"))
    )
    (net (code "56") (name "RD11") (class "Default")
      (node (ref "IC3") (pin "71") (pinfunction "EMDC/IC4/PMCS1/PMA14/RD11_71") (pintype "bidirectional"))
      (node (ref "SV1") (pin "3") (pinfunction "3_3") (pintype "passive"))
    )
    (net (code "57") (name "RD12") (class "Default")
      (node (ref "IC3") (pin "79") (pinfunction "ETXD2/IC5/PMD12/RD12_79") (pintype "bidirectional"))
      (node (ref "SV1") (pin "10") (pinfunction "10_10") (pintype "passive"))
    )
    (net (code "58") (name "RD13") (class "Default")
      (node (ref "IC3") (pin "80") (pinfunction "ETXD3/CN19/PMD13/RD13_80") (pintype "bidirectional"))
      (node (ref "SV1") (pin "9") (pinfunction "9_9") (pintype "passive"))
    )
    (net (code "59") (name "RE0") (class "Default")
      (node (ref "IC3") (pin "93") (pinfunction "RE0/PMD0_93") (pintype "bidirectional"))
      (node (ref "SV1") (pin "22") (pinfunction "22_22") (pintype "passive"))
    )
    (net (code "60") (name "RE1") (class "Default")
      (node (ref "IC3") (pin "94") (pinfunction "RE1/PMD1_94") (pintype "bidirectional"))
      (node (ref "SV1") (pin "21") (pinfunction "21_21") (pintype "passive"))
    )
    (net (code "61") (name "RE2") (class "Default")
      (node (ref "IC3") (pin "98") (pinfunction "RE2/PMD2_98") (pintype "bidirectional"))
      (node (ref "SV1") (pin "25") (pinfunction "25_25") (pintype "passive"))
    )
    (net (code "62") (name "RE3") (class "Default")
      (node (ref "IC3") (pin "99") (pinfunction "RE3/PMD3_99") (pintype "bidirectional"))
      (node (ref "SV1") (pin "28") (pinfunction "28_28") (pintype "passive"))
    )
    (net (code "63") (name "RE4") (class "Default")
      (node (ref "IC3") (pin "100") (pinfunction "RE4/PMD4_100") (pintype "bidirectional"))
      (node (ref "SV1") (pin "27") (pinfunction "27_27") (pintype "passive"))
    )
    (net (code "64") (name "RE5") (class "Default")
      (node (ref "IC3") (pin "3") (pinfunction "RE5/PMD5_3") (pintype "bidirectional"))
      (node (ref "SV1") (pin "29") (pinfunction "29_29") (pintype "passive"))
    )
    (net (code "65") (name "RE6") (class "Default")
      (node (ref "IC3") (pin "4") (pinfunction "RE6/PMD6_4") (pintype "bidirectional"))
      (node (ref "SV1") (pin "32") (pinfunction "32_32") (pintype "passive"))
    )
    (net (code "66") (name "RE7") (class "Default")
      (node (ref "IC3") (pin "5") (pinfunction "RE7/PMD7_5") (pintype "bidirectional"))
      (node (ref "SV1") (pin "31") (pinfunction "31_31") (pintype "passive"))
    )
    (net (code "67") (name "RF0") (class "Default")
      (node (ref "IC3") (pin "87") (pinfunction "C1RX/ETXD1/PMD11/RF0_87") (pintype "bidirectional"))
      (node (ref "SV1") (pin "16") (pinfunction "16_16") (pintype "passive"))
    )
    (net (code "68") (name "RF1") (class "Default")
      (node (ref "IC3") (pin "88") (pinfunction "C1TX/ETXD0/PMD10/RF1_88") (pintype "bidirectional"))
      (node (ref "SV1") (pin "15") (pinfunction "15_15") (pintype "passive"))
    )
    (net (code "69") (name "RG0") (class "Default")
      (node (ref "IC3") (pin "90") (pinfunction "C2RX/PMD8/RG0_90") (pintype "bidirectional"))
      (node (ref "SV1") (pin "17") (pinfunction "17_17") (pintype "passive"))
    )
    (net (code "70") (name "RG1") (class "Default")
      (node (ref "IC3") (pin "89") (pinfunction "C2TX/ETXERR/PMD9/RG1_89") (pintype "bidirectional"))
      (node (ref "SV1") (pin "18") (pinfunction "18_18") (pintype "passive"))
    )
    (net (code "71") (name "RG6") (class "Default")
      (node (ref "IC3") (pin "10") (pinfunction "ECOL/U2BTX/U2ARTS/PMA5/CN8/SCK2/RG6_10") (pintype "bidirectional"))
    )
    (net (code "72") (name "RG7") (class "Default")
      (node (ref "IC3") (pin "11") (pinfunction "ECRS/SDA2A/U2ARX/PMA4/CN9/SDI2A/RG7_11") (pintype "bidirectional"))
    )
    (net (code "73") (name "RG8") (class "Default")
      (node (ref "IC3") (pin "12") (pinfunction "ERXDV/SCL2A/U2ATX/PMA3/CN10/SDO2A/RG8_12") (pintype "bidirectional"))
    )
    (net (code "74") (name "RG12") (class "Default")
      (node (ref "IC3") (pin "96") (pinfunction "TRD1/RG12_96") (pintype "bidirectional"))
      (node (ref "SV1") (pin "23") (pinfunction "23_23") (pintype "passive"))
    )
    (net (code "75") (name "RG13") (class "Default")
      (node (ref "IC3") (pin "97") (pinfunction "TRD0/RG13_97") (pintype "bidirectional"))
      (node (ref "SV1") (pin "26") (pinfunction "26_26") (pintype "passive"))
    )
    (net (code "76") (name "RG14") (class "Default")
      (node (ref "IC3") (pin "95") (pinfunction "TRD2/RG14_95") (pintype "bidirectional"))
      (node (ref "SV1") (pin "24") (pinfunction "24_24") (pintype "passive"))
    )
    (net (code "77") (name "RG15") (class "Default")
      (node (ref "IC3") (pin "1") (pinfunction "AERXERR/RG15_1") (pintype "bidirectional"))
      (node (ref "SV1") (pin "30") (pinfunction "30_30") (pintype "passive"))
    )
    (net (code "78") (name "RXD") (class "Default")
      (node (ref "IC3") (pin "47") (pinfunction "AETXD0/SS1A/U1BRX/U1ACTS/CN20/RD14_47") (pintype "bidirectional"))
      (node (ref "JP3") (pin "3") (pinfunction "3_3") (pintype "passive"))
    )
    (net (code "79") (name "SCK") (class "Default")
      (node (ref "IC3") (pin "39") (pinfunction "AC1TX/SCK3A/U3BTX/U3ARTS/RF13_39") (pintype "bidirectional"))
      (node (ref "IC4") (pin "P$8") (pinfunction "SCK_P$8") (pintype "input"))
      (node (ref "U$2") (pin "6") (pinfunction "SCK_6") (pintype "bidirectional"))
      (node (ref "U1") (pin "5") (pinfunction "SCK_5") (pintype "bidirectional"))
    )
    (net (code "80") (name "SD_CS") (class "Default")
      (node (ref "IC3") (pin "51") (pinfunction "USBID/RF3_51") (pintype "bidirectional"))
      (node (ref "R11") (pin "1") (pinfunction "1_1") (pintype "passive"))
      (node (ref "U1") (pin "2") (pinfunction "CS_2") (pintype "bidirectional"))
    )
    (net (code "81") (name "SD_PRESENT") (class "Default")
      (node (ref "IC3") (pin "52") (pinfunction "SDA1A/SDI1A/U1ARX/RF2_52") (pintype "bidirectional"))
      (node (ref "R8") (pin "1") (pinfunction "1_1") (pintype "passive"))
      (node (ref "U1") (pin "CD1") (pinfunction "SHIELD_CD1") (pintype "bidirectional"))
    )
    (net (code "82") (name "TPIN_N") (class "Default")
      (node (ref "IC4") (pin "P$12") (pinfunction "TPIN-_P$12") (pintype "input"))
      (node (ref "R2") (pin "2") (pinfunction "2_2") (pintype "passive"))
      (node (ref "RJ1") (pin "RD-") (pinfunction "RD-_RD-") (pintype "bidirectional"))
    )
    (net (code "83") (name "TPIN_P") (class "Default")
      (node (ref "IC4") (pin "P$13") (pinfunction "TPIN+_P$13") (pintype "input"))
      (node (ref "R3") (pin "1") (pinfunction "1_1") (pintype "passive"))
      (node (ref "RJ1") (pin "RD+") (pinfunction "RD+_RD+") (pintype "bidirectional"))
    )
    (net (code "84") (name "TPOUT_N") (class "Default")
      (node (ref "IC4") (pin "P$16") (pinfunction "TPOUT-_P$16") (pintype "output"))
      (node (ref "R5") (pin "2") (pinfunction "2_2") (pintype "passive"))
      (node (ref "RJ1") (pin "TD-") (pinfunction "TD-_TD-") (pintype "bidirectional"))
    )
    (net (code "85") (name "TPOUT_P") (class "Default")
      (node (ref "IC4") (pin "P$17") (pinfunction "TPOUT+_P$17") (pintype "output"))
      (node (ref "R4") (pin "1") (pinfunction "1_1") (pintype "passive"))
      (node (ref "RJ1") (pin "TD+") (pinfunction "TD+_TD+") (pintype "bidirectional"))
    )
    (net (code "86") (name "TXD") (class "Default")
      (node (ref "IC3") (pin "48") (pinfunction "AETXD1/SCK1A/U1BTX/U1ARTS/CN21/BCLK1/RD15_48") (pintype "bidirectional"))
      (node (ref "JP3") (pin "2") (pinfunction "2_2") (pintype "passive"))
    )
    (net (code "87") (name "VBUS") (class "Default")
      (node (ref "C12") (pin "+") (pinfunction "+_+") (pintype "passive"))
      (node (ref "C13") (pin "1") (pinfunction "1_1") (pintype "passive"))
      (node (ref "C27") (pin "1") (pinfunction "1_1") (pintype "passive"))
      (node (ref "C30") (pin "+") (pinfunction "+_+") (pintype "passive"))
      (node (ref "C5") (pin "+") (pinfunction "+_+") (pintype "passive"))
      (node (ref "F1") (pin "2") (pinfunction "2_2") (pintype "passive"))
      (node (ref "IC1") (pin "5") (pinfunction "VBUS_5") (pintype "bidirectional"))
      (node (ref "IC2") (pin "3") (pinfunction "IN_3") (pintype "input"))
      (node (ref "IC3") (pin "54") (pinfunction "VBUS_54") (pintype "bidirectional"))
      (node (ref "SG1") (pin "+") (pinfunction "1_+") (pintype "passive"))
      (node (ref "X3") (pin "1") (pinfunction "1_1") (pintype "passive"))
      (node (ref "X4") (pin "2") (pinfunction "S_2") (pintype "passive"))
    )
    (net (code "88") (name "unconnected-(IC3-AC1RX{slash}SS3A{slash}U3BRX{slash}U3ACTS{slash}RF12-Pad40)") (class "Default")
      (node (ref "IC3") (pin "40") (pinfunction "AC1RX/SS3A/U3BRX/U3ACTS/RF12_40") (pintype "bidirectional"))
    )
    (net (code "89") (name "unconnected-(IC3-ERXCLK{slash}SS2A{slash}U2BRX{slash}U2ACTS{slash}PMA2{slash}CN11{slash}RG9-Pad14)") (class "Default")
      (node (ref "IC3") (pin "14") (pinfunction "ERXCLK/SS2A/U2BRX/U2ACTS/PMA2/CN11/RG9_14") (pintype "bidirectional"))
    )
    (net (code "90") (name "unconnected-(IC3-RA0{slash}TMS-Pad17)") (class "Default")
      (node (ref "IC3") (pin "17") (pinfunction "RA0/TMS_17") (pintype "bidirectional"))
    )
    (net (code "91") (name "unconnected-(IC3-RA2{slash}SCL2-Pad58)") (class "Default")
      (node (ref "IC3") (pin "58") (pinfunction "RA2/SCL2_58") (pintype "bidirectional"))
    )
    (net (code "92") (name "unconnected-(IC3-RA3{slash}SDA2-Pad59)") (class "Default")
      (node (ref "IC3") (pin "59") (pinfunction "RA3/SDA2_59") (pintype "bidirectional"))
    )
    (net (code "93") (name "unconnected-(IC3-RA4{slash}TDI-Pad60)") (class "Default")
      (node (ref "IC3") (pin "60") (pinfunction "RA4/TDI_60") (pintype "bidirectional"))
    )
    (net (code "94") (name "unconnected-(IC3-RA5{slash}TDO-Pad61)") (class "Default")
      (node (ref "IC3") (pin "61") (pinfunction "RA5/TDO_61") (pintype "bidirectional"))
    )
    (net (code "95") (name "unconnected-(IC3-RA9{slash}VR-{slash}PMA7{slash}CVREF-{slash}AERXD2-Pad28)") (class "Default")
      (node (ref "IC3") (pin "28") (pinfunction "RA9/VR-/PMA7/CVREF-/AERXD2_28") (pintype "bidirectional"))
    )
    (net (code "96") (name "unconnected-(IC3-RA10{slash}VR+{slash}CVREF+{slash}AERXD3{slash}PMA6-Pad29)") (class "Default")
      (node (ref "IC3") (pin "29") (pinfunction "RA10/VR+/CVREF+/AERXD3/PMA6_29") (pintype "bidirectional"))
    )
    (net (code "97") (name "unconnected-(IC3-RB2{slash}AN2{slash}CN4{slash}C2IN--Pad23)") (class "Default")
      (node (ref "IC3") (pin "23") (pinfunction "RB2/AN2/CN4/C2IN-_23") (pintype "bidirectional"))
    )
    (net (code "98") (name "unconnected-(IC3-RB3{slash}AN3{slash}CN5{slash}C2IN+-Pad22)") (class "Default")
      (node (ref "IC3") (pin "22") (pinfunction "RB3/AN3/CN5/C2IN+_22") (pintype "bidirectional"))
    )
    (net (code "99") (name "unconnected-(IC3-RB4{slash}AN4{slash}CN6{slash}C1IN--Pad21)") (class "Default")
      (node (ref "IC3") (pin "21") (pinfunction "RB4/AN4/CN6/C1IN-_21") (pintype "bidirectional"))
    )
    (net (code "100") (name "unconnected-(IC3-RB5{slash}AN5{slash}CN7{slash}C1IN+{slash}VBUSON-Pad20)") (class "Default")
      (node (ref "IC3") (pin "20") (pinfunction "RB5/AN5/CN7/C1IN+/VBUSON_20") (pintype "bidirectional"))
    )
    (net (code "101") (name "unconnected-(IC3-RB6{slash}AN6{slash}PGC2{slash}OCFA-Pad26)") (class "Default")
      (node (ref "IC3") (pin "26") (pinfunction "RB6/AN6/PGC2/OCFA_26") (pintype "bidirectional"))
    )
    (net (code "102") (name "unconnected-(IC3-RB7{slash}AN7{slash}PGD2-Pad27)") (class "Default")
      (node (ref "IC3") (pin "27") (pinfunction "RB7/AN7/PGD2_27") (pintype "bidirectional"))
    )
    (net (code "103") (name "unconnected-(IC3-RB8{slash}AN8{slash}C1OUT-Pad32)") (class "Default")
      (node (ref "IC3") (pin "32") (pinfunction "RB8/AN8/C1OUT_32") (pintype "bidirectional"))
    )
    (net (code "104") (name "unconnected-(IC3-RB9{slash}AN9{slash}C2OUT-Pad33)") (class "Default")
      (node (ref "IC3") (pin "33") (pinfunction "RB9/AN9/C2OUT_33") (pintype "bidirectional"))
    )
    (net (code "105") (name "unconnected-(IC3-RB10{slash}AN10{slash}CVREF{slash}PMA13-Pad34)") (class "Default")
      (node (ref "IC3") (pin "34") (pinfunction "RB10/AN10/CVREF/PMA13_34") (pintype "bidirectional"))
    )
    (net (code "106") (name "unconnected-(IC3-RB11{slash}AN11{slash}PMA12{slash}ERXERR{slash}AETXERR-Pad35)") (class "Default")
      (node (ref "IC3") (pin "35") (pinfunction "RB11/AN11/PMA12/ERXERR/AETXERR_35") (pintype "bidirectional"))
    )
    (net (code "107") (name "unconnected-(IC3-RB12{slash}AN12{slash}PMA11{slash}ERXD0{slash}AECRS-Pad41)") (class "Default")
      (node (ref "IC3") (pin "41") (pinfunction "RB12/AN12/PMA11/ERXD0/AECRS_41") (pintype "bidirectional"))
    )
    (net (code "108") (name "unconnected-(IC3-RB13{slash}AN13{slash}PMA10{slash}ERXD1{slash}AECOL-Pad42)") (class "Default")
      (node (ref "IC3") (pin "42") (pinfunction "RB13/AN13/PMA10/ERXD1/AECOL_42") (pintype "bidirectional"))
    )
    (net (code "109") (name "unconnected-(IC3-RB14{slash}AN14{slash}PMA1{slash}ERXD2{slash}AETXD3{slash}-Pad43)") (class "Default")
      (node (ref "IC3") (pin "43") (pinfunction "RB14/AN14/PMA1/ERXD2/AETXD3/_43") (pintype "bidirectional"))
    )
    (net (code "110") (name "unconnected-(IC3-RB15{slash}AN15{slash}CN12{slash}OCFB{slash}-Pad44)") (class "Default")
      (node (ref "IC3") (pin "44") (pinfunction "RB15/AN15/CN12/OCFB/_44") (pintype "bidirectional"))
    )
    (net (code "111") (name "unconnected-(IC3-RC2{slash}T3CK{slash}AC2TX-Pad7)") (class "Default")
      (node (ref "IC3") (pin "7") (pinfunction "RC2/T3CK/AC2TX_7") (pintype "bidirectional"))
    )
    (net (code "112") (name "unconnected-(IC3-RE8{slash}INT1{slash}AERXD0-Pad18)") (class "Default")
      (node (ref "IC3") (pin "18") (pinfunction "RE8/INT1/AERXD0_18") (pintype "bidirectional"))
    )
    (net (code "113") (name "unconnected-(IC3-RE9{slash}INT2{slash}AERXD1-Pad19)") (class "Default")
      (node (ref "IC3") (pin "19") (pinfunction "RE9/INT2/AERXD1_19") (pintype "bidirectional"))
    )
    (net (code "114") (name "unconnected-(IC4-CLKOUT-PadP$3)") (class "Default")
      (node (ref "IC4") (pin "P$3") (pinfunction "CLKOUT_P$3") (pintype "output"))
    )
    (net (code "115") (name "unconnected-(IC4-NC*-PadP$5)") (class "Default")
      (node (ref "IC4") (pin "P$5") (pinfunction "NC*_P$5") (pintype "output"))
    )
    (net (code "116") (name "unconnected-(IC4-~{INT}-PadP$4)") (class "Default")
      (node (ref "IC4") (pin "P$4") (pinfunction "~{INT}_P$4") (pintype "output"))
    )
    (net (code "117") (name "unconnected-(JP2-Pad2)") (class "Default")
      (node (ref "JP2") (pin "2") (pinfunction "2_2") (pintype "passive"))
    )
    (net (code "118") (name "unconnected-(JP2-Pad6)") (class "Default")
      (node (ref "JP2") (pin "6") (pinfunction "6_6") (pintype "passive"))
    )
    (net (code "119") (name "unconnected-(JP5-D+-PadD+1)") (class "Default")
      (node (ref "JP5") (pin "D+1") (pinfunction "D+_D+1") (pintype "bidirectional"))
    )
    (net (code "120") (name "unconnected-(JP5-D--PadD-1)") (class "Default")
      (node (ref "JP5") (pin "D-1") (pinfunction "D-_D-1") (pintype "bidirectional"))
    )
    (net (code "121") (name "unconnected-(JP5-ID-PadID1)") (class "Default")
      (node (ref "JP5") (pin "ID1") (pinfunction "ID_ID1") (pintype "bidirectional"))
    )
    (net (code "122") (name "unconnected-(RJ1-PadNC)") (class "Default")
      (node (ref "RJ1") (pin "NC") (pinfunction "NC_NC") (pintype "bidirectional"))
    )
    (net (code "123") (name "unconnected-(RJ1-PadP5)") (class "Default")
      (node (ref "RJ1") (pin "P5") (pinfunction "P5_P5") (pintype "bidirectional"))
    )
    (net (code "124") (name "unconnected-(U1-NC-Pad1)") (class "Default")
      (node (ref "U1") (pin "1") (pinfunction "NC_1") (pintype "bidirectional"))
    )
    (net (code "125") (name "unconnected-(U1-RSV-Pad8)") (class "Default")
      (node (ref "U1") (pin "8") (pinfunction "RSV_8") (pintype "bidirectional"))
    )
  )
)
